# 23128_ROM-el_v1_1.net
KiCad netlist of a schematic drawn in EAGLE
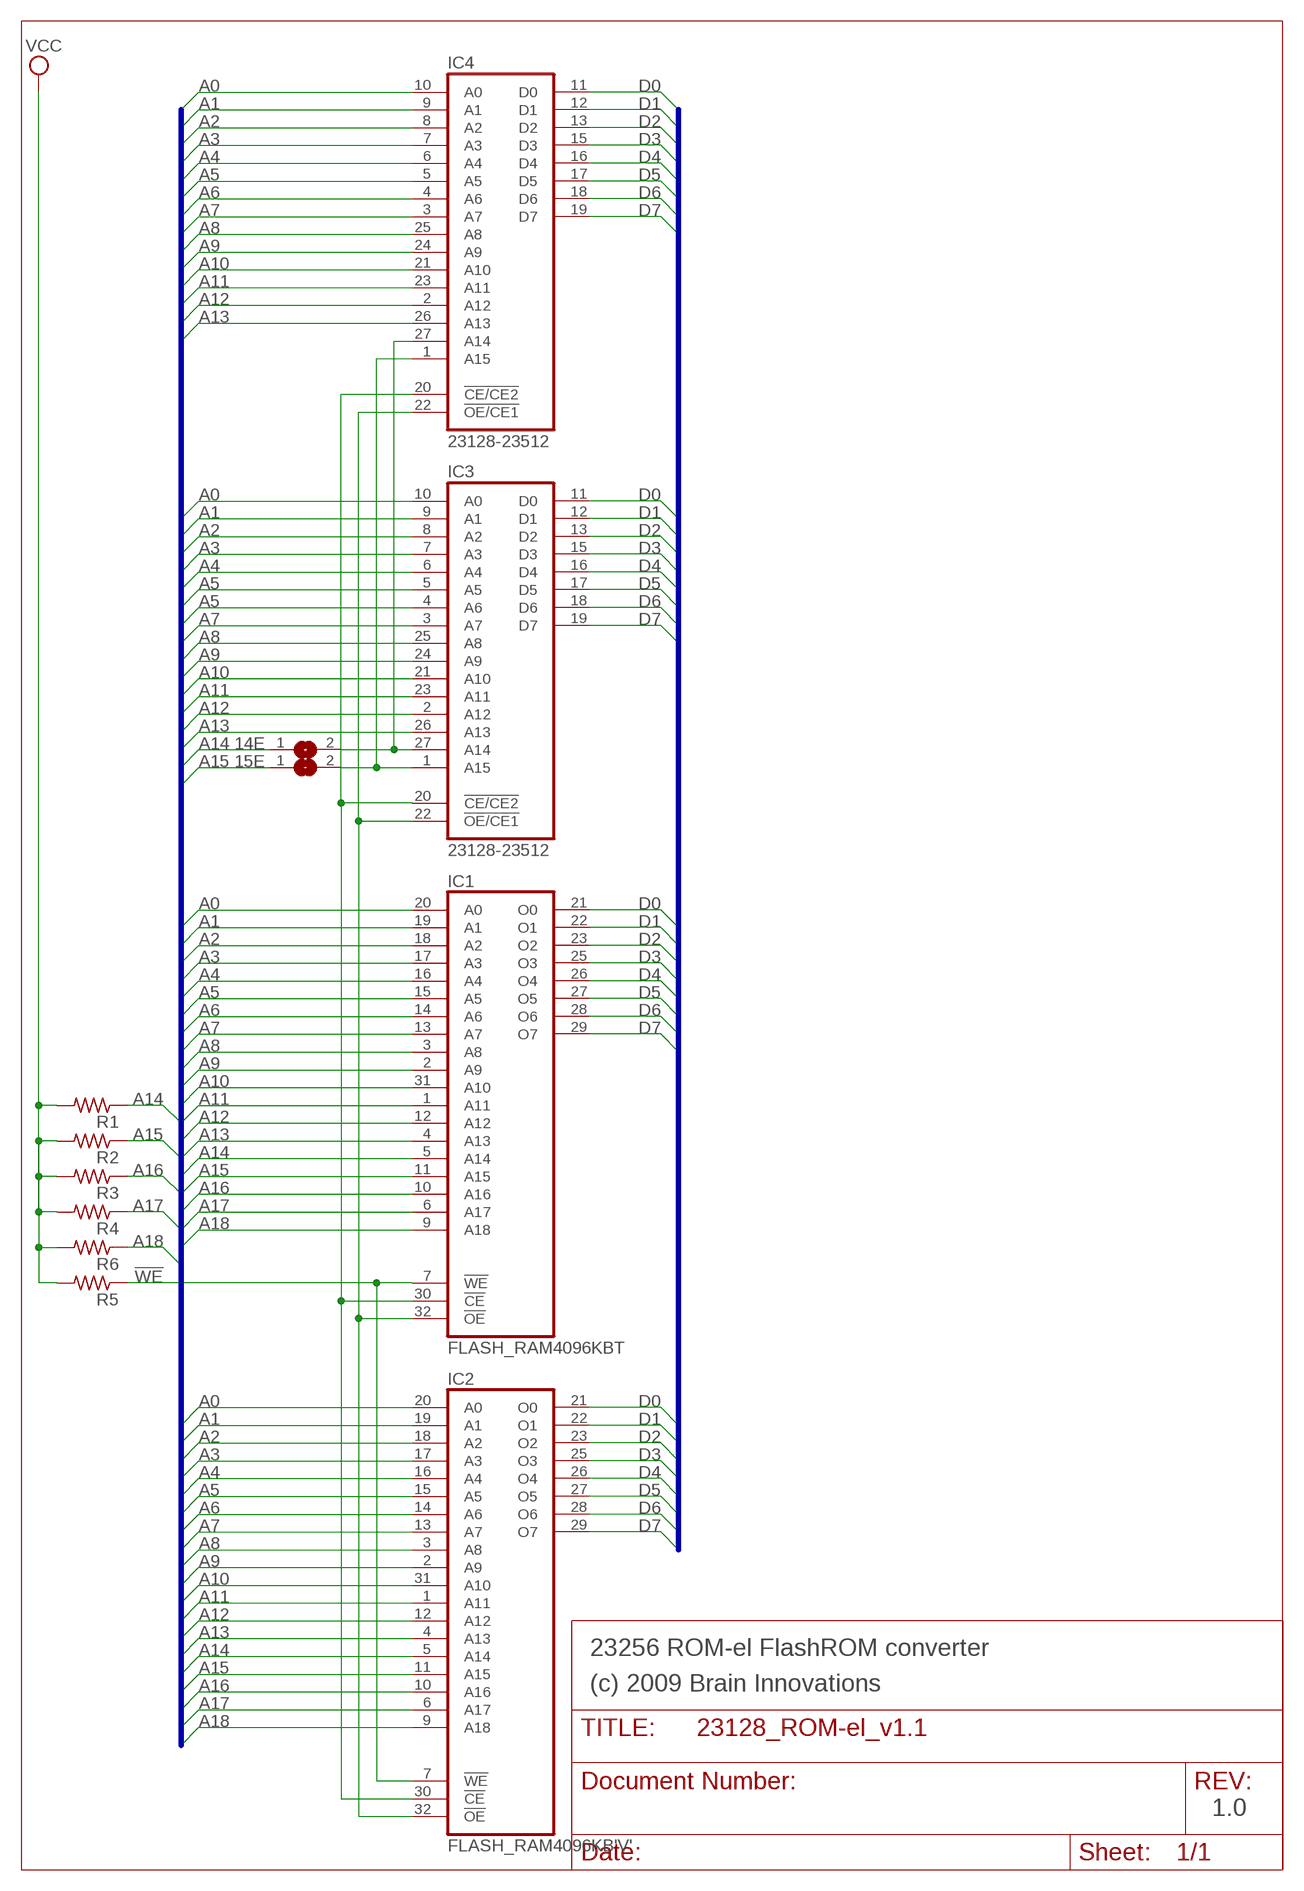
[diagram p0: schematic, sheet 1]

(export (version "E")
  (design (tool "Eeschema 10.0.6"))
  (components
    (comp (ref "14E") (value "SJ") (footprint "eagle-import:SJ") (libsource (lib "eagle-import") (part "SJ")))
    (comp (ref "15E")
      (value "15E")
      (footprint "eagle-import:SJ")
      (libsource (lib "eagle-import") (part "SJ"))
    )
    (comp (ref "IC1")
      (value "FLASH_RAM4096KBT")
      (footprint "eagle-import:TSOP32")
      (libsource (lib "eagle-import") (part "FLASH_RAM4096KB'T'"))
    )
    (comp (ref "IC2")
      (value "FLASH_RAM4096KB'V'")
      (footprint "eagle-import:VSOP32")
      (libsource (lib "eagle-import") (part "FLASH_RAM4096KB'V'"))
    )
    (comp (ref "IC3")
      (value "23128-23512")
      (footprint "eagle-import:DIL28-ROUNDPAD")
      (libsource (lib "eagle-import") (part "23512-RP"))
    )
    (comp (ref "IC4")
      (value "23128-23512")
      (footprint "eagle-import:DIL28-SMD-REVERSE")
      (libsource (lib "eagle-import") (part "23512-SB"))
    )
    (comp (ref "R1")
      (value "R-US_R0805")
      (footprint "eagle-import:R0805")
      (libsource (lib "eagle-import") (part "R-US_R0805"))
    )
    (comp (ref "R2")
      (value "R-US_R0805")
      (footprint "eagle-import:R0805")
      (libsource (lib "eagle-import") (part "R-US_R0805"))
    )
    (comp (ref "R3")
      (value "R-US_R0805")
      (footprint "eagle-import:R0805")
      (libsource (lib "eagle-import") (part "R-US_R0805"))
    )
    (comp (ref "R4")
      (value "R-US_R0805")
      (footprint "eagle-import:R0805")
      (libsource (lib "eagle-import") (part "R-US_R0805"))
    )
    (comp (ref "R5")
      (value "R-US_R0805")
      (footprint "eagle-import:R0805")
      (libsource (lib "eagle-import") (part "R-US_R0805"))
    )
    (comp (ref "R6")
      (value "R-US_R0805")
      (footprint "eagle-import:R0805")
      (libsource (lib "eagle-import") (part "R-US_R0805"))
    )
  )
  (nets
    (net (code "1") (name "/A0") (class "Default")
      (node (ref "IC1") (pin "20") (pinfunction "A0_20") (pintype "input"))
      (node (ref "IC2") (pin "20") (pinfunction "A0_20") (pintype "input"))
      (node (ref "IC3") (pin "10") (pinfunction "A0_10") (pintype "input"))
      (node (ref "IC4") (pin "10") (pinfunction "A0_10") (pintype "input"))
    )
    (net (code "2") (name "/A1") (class "Default")
      (node (ref "IC1") (pin "19") (pinfunction "A1_19") (pintype "input"))
      (node (ref "IC2") (pin "19") (pinfunction "A1_19") (pintype "input"))
      (node (ref "IC3") (pin "9") (pinfunction "A1_9") (pintype "input"))
      (node (ref "IC4") (pin "9") (pinfunction "A1_9") (pintype "input"))
    )
    (net (code "3") (name "/A2") (class "Default")
      (node (ref "IC1") (pin "18") (pinfunction "A2_18") (pintype "input"))
      (node (ref "IC2") (pin "18") (pinfunction "A2_18") (pintype "input"))
      (node (ref "IC3") (pin "8") (pinfunction "A2_8") (pintype "input"))
      (node (ref "IC4") (pin "8") (pinfunction "A2_8") (pintype "input"))
    )
    (net (code "4") (name "/A3") (class "Default")
      (node (ref "IC1") (pin "17") (pinfunction "A3_17") (pintype "input"))
      (node (ref "IC2") (pin "17") (pinfunction "A3_17") (pintype "input"))
      (node (ref "IC3") (pin "7") (pinfunction "A3_7") (pintype "input"))
      (node (ref "IC4") (pin "7") (pinfunction "A3_7") (pintype "input"))
    )
    (net (code "5") (name "/A4") (class "Default")
      (node (ref "IC1") (pin "16") (pinfunction "A4_16") (pintype "input"))
      (node (ref "IC2") (pin "16") (pinfunction "A4_16") (pintype "input"))
      (node (ref "IC3") (pin "6") (pinfunction "A4_6") (pintype "input"))
      (node (ref "IC4") (pin "6") (pinfunction "A4_6") (pintype "input"))
    )
    (net (code "6") (name "/A5") (class "Default")
      (node (ref "IC1") (pin "15") (pinfunction "A5_15") (pintype "input"))
      (node (ref "IC2") (pin "15") (pinfunction "A5_15") (pintype "input"))
      (node (ref "IC3") (pin "5") (pinfunction "A5_5") (pintype "input"))
      (node (ref "IC4") (pin "5") (pinfunction "A5_5") (pintype "input"))
    )
    (net (code "7") (name "/A6") (class "Default")
      (node (ref "IC1") (pin "14") (pinfunction "A6_14") (pintype "input"))
      (node (ref "IC2") (pin "14") (pinfunction "A6_14") (pintype "input"))
      (node (ref "IC3") (pin "4") (pinfunction "A6_4") (pintype "input"))
      (node (ref "IC4") (pin "4") (pinfunction "A6_4") (pintype "input"))
    )
    (net (code "8") (name "/A7") (class "Default")
      (node (ref "IC1") (pin "13") (pinfunction "A7_13") (pintype "input"))
      (node (ref "IC2") (pin "13") (pinfunction "A7_13") (pintype "input"))
      (node (ref "IC3") (pin "3") (pinfunction "A7_3") (pintype "input"))
      (node (ref "IC4") (pin "3") (pinfunction "A7_3") (pintype "input"))
    )
    (net (code "9") (name "/A8") (class "Default")
      (node (ref "IC1") (pin "3") (pinfunction "A8_3") (pintype "input"))
      (node (ref "IC2") (pin "3") (pinfunction "A8_3") (pintype "input"))
      (node (ref "IC3") (pin "25") (pinfunction "A8_25") (pintype "input"))
      (node (ref "IC4") (pin "25") (pinfunction "A8_25") (pintype "input"))
    )
    (net (code "10") (name "/A9") (class "Default")
      (node (ref "IC1") (pin "2") (pinfunction "A9_2") (pintype "input"))
      (node (ref "IC2") (pin "2") (pinfunction "A9_2") (pintype "input"))
      (node (ref "IC3") (pin "24") (pinfunction "A9_24") (pintype "input"))
      (node (ref "IC4") (pin "24") (pinfunction "A9_24") (pintype "input"))
    )
    (net (code "11") (name "/A10") (class "Default")
      (node (ref "IC1") (pin "31") (pinfunction "A10_31") (pintype "input"))
      (node (ref "IC2") (pin "31") (pinfunction "A10_31") (pintype "input"))
      (node (ref "IC3") (pin "21") (pinfunction "A10_21") (pintype "input"))
      (node (ref "IC4") (pin "21") (pinfunction "A10_21") (pintype "input"))
    )
    (net (code "12") (name "/A11") (class "Default")
      (node (ref "IC1") (pin "1") (pinfunction "A11_1") (pintype "input"))
      (node (ref "IC2") (pin "1") (pinfunction "A11_1") (pintype "input"))
      (node (ref "IC3") (pin "23") (pinfunction "A11_23") (pintype "input"))
      (node (ref "IC4") (pin "23") (pinfunction "A11_23") (pintype "input"))
    )
    (net (code "13") (name "/A12") (class "Default")
      (node (ref "IC1") (pin "12") (pinfunction "A12_12") (pintype "input"))
      (node (ref "IC2") (pin "12") (pinfunction "A12_12") (pintype "input"))
      (node (ref "IC3") (pin "2") (pinfunction "A12_2") (pintype "input"))
      (node (ref "IC4") (pin "2") (pinfunction "A12_2") (pintype "input"))
    )
    (net (code "14") (name "/A13") (class "Default")
      (node (ref "IC1") (pin "4") (pinfunction "A13_4") (pintype "input"))
      (node (ref "IC2") (pin "4") (pinfunction "A13_4") (pintype "input"))
      (node (ref "IC3") (pin "26") (pinfunction "A13_26") (pintype "input"))
      (node (ref "IC4") (pin "26") (pinfunction "A13_26") (pintype "input"))
    )
    (net (code "15") (name "/A14") (class "Default")
      (node (ref "14E") (pin "1") (pinfunction "1_1") (pintype "passive"))
      (node (ref "IC1") (pin "5") (pinfunction "A14_5") (pintype "input"))
      (node (ref "IC2") (pin "5") (pinfunction "A14_5") (pintype "input"))
      (node (ref "R1") (pin "1") (pinfunction "1_1") (pintype "passive"))
    )
    (net (code "16") (name "/A15") (class "Default")
      (node (ref "15E") (pin "1") (pinfunction "1_1") (pintype "passive"))
      (node (ref "IC1") (pin "11") (pinfunction "A15_11") (pintype "input"))
      (node (ref "IC2") (pin "11") (pinfunction "A15_11") (pintype "input"))
      (node (ref "R2") (pin "1") (pinfunction "1_1") (pintype "passive"))
    )
    (net (code "17") (name "/A16") (class "Default")
      (node (ref "IC1") (pin "10") (pinfunction "A16_10") (pintype "input"))
      (node (ref "IC2") (pin "10") (pinfunction "A16_10") (pintype "input"))
      (node (ref "R3") (pin "1") (pinfunction "1_1") (pintype "passive"))
    )
    (net (code "18") (name "/A17") (class "Default")
      (node (ref "IC1") (pin "6") (pinfunction "A17_6") (pintype "input"))
      (node (ref "IC2") (pin "6") (pinfunction "A17_6") (pintype "input"))
      (node (ref "R4") (pin "1") (pinfunction "1_1") (pintype "passive"))
    )
    (net (code "19") (name "/A18") (class "Default")
      (node (ref "IC1") (pin "9") (pinfunction "A18_9") (pintype "input"))
      (node (ref "IC2") (pin "9") (pinfunction "A18_9") (pintype "input"))
      (node (ref "R6") (pin "1") (pinfunction "1_1") (pintype "passive"))
    )
    (net (code "20") (name "/D0") (class "Default")
      (node (ref "IC1") (pin "21") (pinfunction "O0_21") (pintype "tri_state"))
      (node (ref "IC2") (pin "21") (pinfunction "O0_21") (pintype "tri_state"))
      (node (ref "IC3") (pin "11") (pinfunction "D0_11") (pintype "tri_state"))
      (node (ref "IC4") (pin "11") (pinfunction "D0_11") (pintype "tri_state"))
    )
    (net (code "21") (name "/D1") (class "Default")
      (node (ref "IC1") (pin "22") (pinfunction "O1_22") (pintype "tri_state"))
      (node (ref "IC2") (pin "22") (pinfunction "O1_22") (pintype "tri_state"))
      (node (ref "IC3") (pin "12") (pinfunction "D1_12") (pintype "tri_state"))
      (node (ref "IC4") (pin "12") (pinfunction "D1_12") (pintype "tri_state"))
    )
    (net (code "22") (name "/D2") (class "Default")
      (node (ref "IC1") (pin "23") (pinfunction "O2_23") (pintype "tri_state"))
      (node (ref "IC2") (pin "23") (pinfunction "O2_23") (pintype "tri_state"))
      (node (ref "IC3") (pin "13") (pinfunction "D2_13") (pintype "tri_state"))
      (node (ref "IC4") (pin "13") (pinfunction "D2_13") (pintype "tri_state"))
    )
    (net (code "23") (name "/D3") (class "Default")
      (node (ref "IC1") (pin "25") (pinfunction "O3_25") (pintype "tri_state"))
      (node (ref "IC2") (pin "25") (pinfunction "O3_25") (pintype "tri_state"))
      (node (ref "IC3") (pin "15") (pinfunction "D3_15") (pintype "tri_state"))
      (node (ref "IC4") (pin "15") (pinfunction "D3_15") (pintype "tri_state"))
    )
    (net (code "24") (name "/D4") (class "Default")
      (node (ref "IC1") (pin "26") (pinfunction "O4_26") (pintype "tri_state"))
      (node (ref "IC2") (pin "26") (pinfunction "O4_26") (pintype "tri_state"))
      (node (ref "IC3") (pin "16") (pinfunction "D4_16") (pintype "tri_state"))
      (node (ref "IC4") (pin "16") (pinfunction "D4_16") (pintype "tri_state"))
    )
    (net (code "25") (name "/D5") (class "Default")
      (node (ref "IC1") (pin "27") (pinfunction "O5_27") (pintype "tri_state"))
      (node (ref "IC2") (pin "27") (pinfunction "O5_27") (pintype "tri_state"))
      (node (ref "IC3") (pin "17") (pinfunction "D5_17") (pintype "tri_state"))
      (node (ref "IC4") (pin "17") (pinfunction "D5_17") (pintype "tri_state"))
    )
    (net (code "26") (name "/D6") (class "Default")
      (node (ref "IC1") (pin "28") (pinfunction "O6_28") (pintype "tri_state"))
      (node (ref "IC2") (pin "28") (pinfunction "O6_28") (pintype "tri_state"))
      (node (ref "IC3") (pin "18") (pinfunction "D6_18") (pintype "tri_state"))
      (node (ref "IC4") (pin "18") (pinfunction "D6_18") (pintype "tri_state"))
    )
    (net (code "27") (name "/D7") (class "Default")
      (node (ref "IC1") (pin "29") (pinfunction "O7_29") (pintype "tri_state"))
      (node (ref "IC2") (pin "29") (pinfunction "O7_29") (pintype "tri_state"))
      (node (ref "IC3") (pin "19") (pinfunction "D7_19") (pintype "tri_state"))
      (node (ref "IC4") (pin "19") (pinfunction "D7_19") (pintype "tri_state"))
    )
    (net (code "28") (name "/~{WE}") (class "Default")
      (node (ref "IC1") (pin "7") (pinfunction "~{WE}_7") (pintype "input"))
      (node (ref "IC2") (pin "7") (pinfunction "~{WE}_7") (pintype "input"))
      (node (ref "R5") (pin "1") (pinfunction "1_1") (pintype "passive"))
    )
    (net (code "29") (name "Net-(IC1A-~{CE})") (class "Default")
      (node (ref "IC1") (pin "30") (pinfunction "~{CE}_30") (pintype "input"))
      (node (ref "IC2") (pin "30") (pinfunction "~{CE}_30") (pintype "input"))
      (node (ref "IC3") (pin "20") (pinfunction "~{CE/CE2}_20") (pintype "input"))
      (node (ref "IC4") (pin "20") (pinfunction "~{CE/CE2}_20") (pintype "input"))
    )
    (net (code "30") (name "Net-(IC1A-~{OE})") (class "Default")
      (node (ref "IC1") (pin "32") (pinfunction "~{OE}_32") (pintype "input"))
      (node (ref "IC2") (pin "32") (pinfunction "~{OE}_32") (pintype "input"))
      (node (ref "IC3") (pin "22") (pinfunction "~{OE/CE1}_22") (pintype "input"))
      (node (ref "IC4") (pin "22") (pinfunction "~{OE/CE1}_22") (pintype "input"))
    )
    (net (code "31") (name "Net-(IC3A-A14)") (class "Default")
      (node (ref "14E") (pin "2") (pinfunction "2_2") (pintype "passive"))
      (node (ref "IC3") (pin "27") (pinfunction "A14_27") (pintype "input"))
      (node (ref "IC4") (pin "27") (pinfunction "A14_27") (pintype "input"))
    )
    (net (code "32") (name "Net-(IC3A-A15)") (class "Default")
      (node (ref "15E") (pin "2") (pinfunction "2_2") (pintype "passive"))
      (node (ref "IC3") (pin "1") (pinfunction "A15_1") (pintype "input"))
      (node (ref "IC4") (pin "1") (pinfunction "A15_1") (pintype "input"))
    )
    (net (code "33") (name "VCC") (class "Default")
      (node (ref "R1") (pin "2") (pinfunction "2_2") (pintype "passive"))
      (node (ref "R2") (pin "2") (pinfunction "2_2") (pintype "passive"))
      (node (ref "R3") (pin "2") (pinfunction "2_2") (pintype "passive"))
      (node (ref "R4") (pin "2") (pinfunction "2_2") (pintype "passive"))
      (node (ref "R5") (pin "2") (pinfunction "2_2") (pintype "passive"))
      (node (ref "R6") (pin "2") (pinfunction "2_2") (pintype "passive"))
    )
  )
)
